# ltc2943_breakout.net
KiCad netlist of a schematic drawn in EAGLE
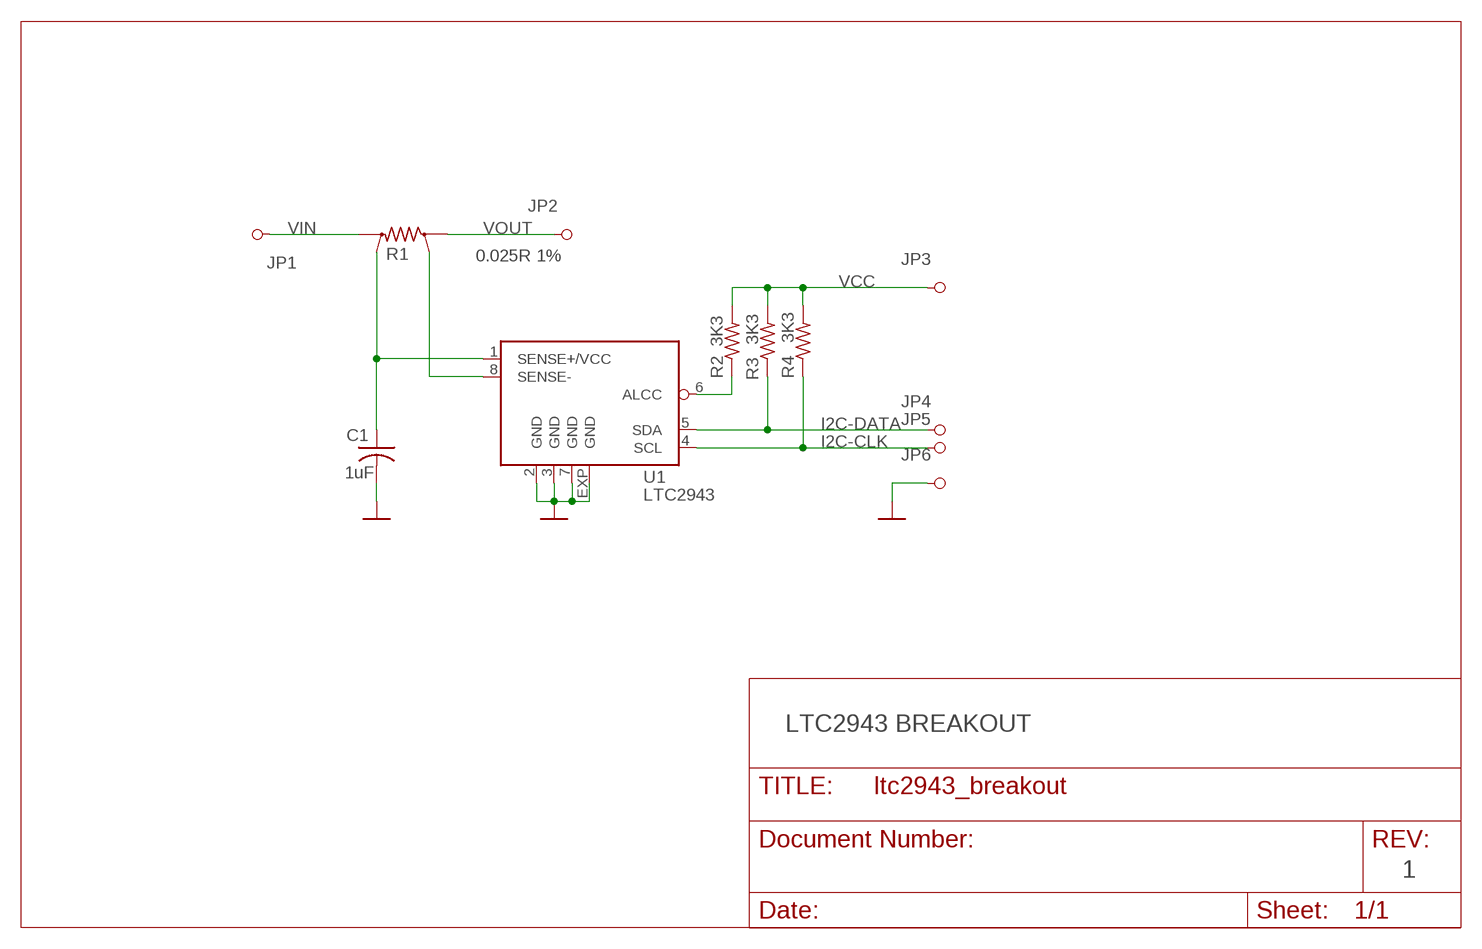
[diagram p0: schematic, sheet 1]

(export (version "E")
  (design (tool "Eeschema 10.0.6"))
  (components
    (comp (ref "C1")
      (value "1uF")
      (footprint "eagle-import:C0603")
      (libsource (lib "eagle-import") (part "CAP-C0603"))
    )
    (comp (ref "JP1")
      (value "PINHD-1X1")
      (footprint "eagle-import:1X01")
      (libsource (lib "eagle-import") (part "PINHD-1X1"))
    )
    (comp (ref "JP2")
      (value "PINHD-1X1")
      (footprint "eagle-import:1X01")
      (libsource (lib "eagle-import") (part "PINHD-1X1"))
    )
    (comp (ref "JP3")
      (value "PINHD-1X1")
      (footprint "eagle-import:1X01")
      (libsource (lib "eagle-import") (part "PINHD-1X1"))
    )
    (comp (ref "JP4")
      (value "PINHD-1X1")
      (footprint "eagle-import:1X01")
      (libsource (lib "eagle-import") (part "PINHD-1X1"))
    )
    (comp (ref "JP5")
      (value "PINHD-1X1")
      (footprint "eagle-import:1X01")
      (libsource (lib "eagle-import") (part "PINHD-1X1"))
    )
    (comp (ref "JP6")
      (value "PINHD-1X1")
      (footprint "eagle-import:1X01")
      (libsource (lib "eagle-import") (part "PINHD-1X1"))
    )
    (comp (ref "R1")
      (value "0.025R 1%")
      (footprint "eagle-import:KELVIN-6432")
      (libsource (lib "eagle-import") (part "RES-SHUNT-6432"))
    )
    (comp (ref "R2")
      (value "3K3")
      (footprint "eagle-import:R0603")
      (libsource (lib "eagle-import") (part "RES-R0603"))
    )
    (comp (ref "R3")
      (value "3K3")
      (footprint "eagle-import:R0603")
      (libsource (lib "eagle-import") (part "RES-R0603"))
    )
    (comp (ref "R4")
      (value "3K3")
      (footprint "eagle-import:R0603")
      (libsource (lib "eagle-import") (part "RES-R0603"))
    )
    (comp (ref "U1")
      (value "LTC2943")
      (footprint "eagle-import:DFN8-3X3")
      (libsource (lib "eagle-import") (part "LTC2943"))
    )
  )
  (nets
    (net (code "1") (name "/I2C-CLK") (class "Default")
      (node (ref "JP5") (pin "1") (pinfunction "1_1") (pintype "passive"))
      (node (ref "R4") (pin "1") (pinfunction "1_1") (pintype "passive"))
      (node (ref "U1") (pin "4") (pinfunction "SCL_4") (pintype "input"))
    )
    (net (code "2") (name "/I2C-DATA") (class "Default")
      (node (ref "JP4") (pin "1") (pinfunction "1_1") (pintype "passive"))
      (node (ref "R3") (pin "1") (pinfunction "1_1") (pintype "passive"))
      (node (ref "U1") (pin "5") (pinfunction "SDA_5") (pintype "bidirectional"))
    )
    (net (code "3") (name "/VCC") (class "Default")
      (node (ref "JP3") (pin "1") (pinfunction "1_1") (pintype "passive"))
      (node (ref "R2") (pin "2") (pinfunction "2_2") (pintype "passive"))
      (node (ref "R3") (pin "2") (pinfunction "2_2") (pintype "passive"))
      (node (ref "R4") (pin "2") (pinfunction "2_2") (pintype "passive"))
    )
    (net (code "4") (name "/VIN") (class "Default")
      (node (ref "JP1") (pin "1") (pinfunction "1_1") (pintype "passive"))
      (node (ref "R1") (pin "I2") (pinfunction "I2_I2") (pintype "passive"))
    )
    (net (code "5") (name "/VOUT") (class "Default")
      (node (ref "JP2") (pin "1") (pinfunction "1_1") (pintype "passive"))
      (node (ref "R1") (pin "I1") (pinfunction "I1_I1") (pintype "passive"))
    )
    (net (code "6") (name "GND") (class "Default")
      (node (ref "C1") (pin "2") (pinfunction "2_2") (pintype "passive"))
      (node (ref "JP6") (pin "1") (pinfunction "1_1") (pintype "passive"))
      (node (ref "U1") (pin "2") (pinfunction "GND_2") (pintype "power_in"))
      (node (ref "U1") (pin "3") (pinfunction "GND_3") (pintype "power_in"))
      (node (ref "U1") (pin "7") (pinfunction "GND_7") (pintype "power_in"))
      (node (ref "U1") (pin "EXP") (pinfunction "GND_EXP") (pintype "power_in"))
    )
    (net (code "7") (name "Net-(U1-ALCC)") (class "Default")
      (node (ref "R2") (pin "1") (pinfunction "1_1") (pintype "passive"))
      (node (ref "U1") (pin "6") (pinfunction "ALCC_6") (pintype "open_collector"))
    )
    (net (code "8") (name "Net-(U1-SENSE+{slash}VCC)") (class "Default")
      (node (ref "C1") (pin "1") (pinfunction "1_1") (pintype "passive"))
      (node (ref "R1") (pin "V2") (pinfunction "V2_V2") (pintype "passive"))
      (node (ref "U1") (pin "1") (pinfunction "SENSE+/VCC_1") (pintype "passive"))
    )
    (net (code "9") (name "Net-(U1-SENSE-)") (class "Default")
      (node (ref "R1") (pin "V1") (pinfunction "V1_V1") (pintype "passive"))
      (node (ref "U1") (pin "8") (pinfunction "SENSE-_8") (pintype "passive"))
    )
  )
)
